# TopSheet.net
KiCad netlist of a schematic drawn in Altium Designer
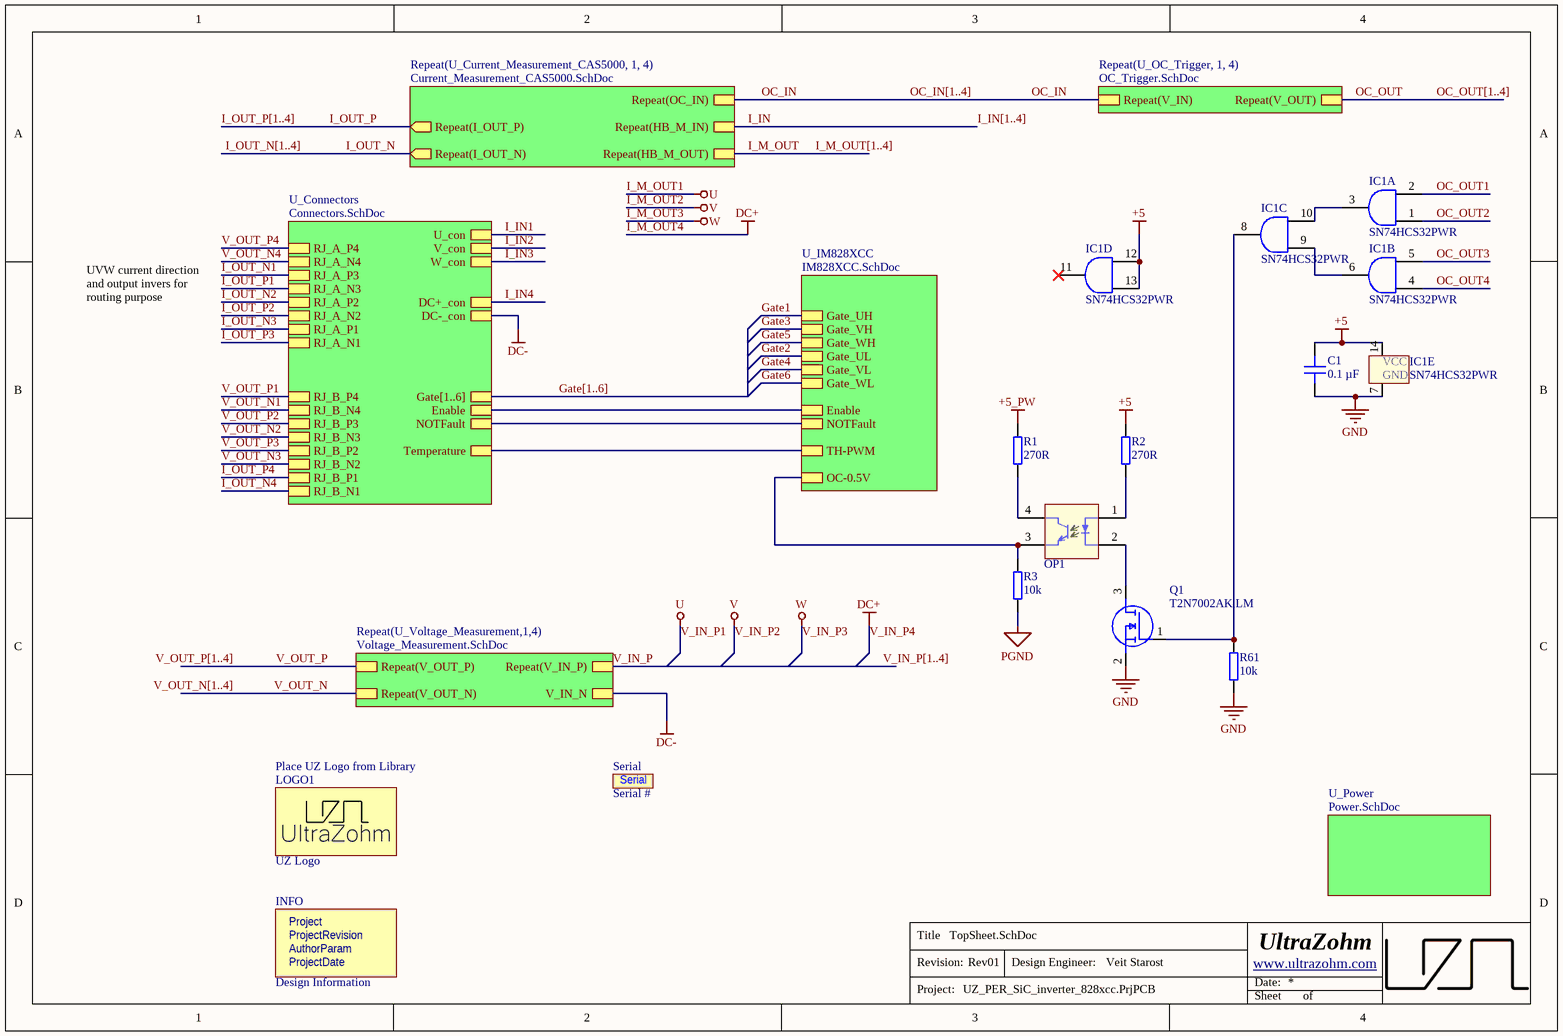
[diagram p0: TopSheet.SchDoc]

(export (version "E")
  (design (tool "Eeschema 10.0.6"))
  (components
    (comp (ref "C1")
      (value "0.1 µF")
      (footprint "C_0603")
      (description "Capacitor 0603, 50 VDC, 0.1 µF, X7R")
      (fields
        (field (name "MANUFACTURER PART NUMBER") "C0603X104K5RAC7411")
        (field (name "MANUFACTURER") "KEMET")
        (field (name "CREATED FROM") "MGremer")
      )
      (libsource (lib "user") (part "Capacitor"))
    )
    (comp (ref "IC1")
      (value "SN74HCS32PWR")
      (footprint "TSSOP-14")
      (description "Logische Gatter Quadruple 2-input OR gates with Schmitt-trigger inputs 14-TSSOP -40 to 125")
      (fields (field (name "MANUFACTURER") "Texas Instruments") (field (name "CREATED FROM") "VStarost"))
      (libsource (lib "") (part "SN74HCS32PWR_1"))
    )
    (comp (ref "INFO")
      (value "Design Information")
      (footprint "Design_info")
      (fields (field (name "MANUFACTURER") "UltraZohm") (field (name "CREATED FROM") "MGremer"))
      (libsource (lib "user") (part "Design_info"))
    )
    (comp (ref "LOGO1")
      (value "UZ Logo")
      (footprint "UZ_Logo_small")
      (fields
        (field (name "MANUFACTURER PART NUMBER") "Logo small")
        (field (name "MANUFACTURER") "UltraZohm")
        (field (name "CREATED") "Jan2021_Liegmann")
        (field (name "CREATED FROM") "MGremer")
      )
      (libsource (lib "user") (part "UZ Logo"))
    )
    (comp (ref "OP1")
      (value "VO617A-2X017T")
      (footprint "SMD4")
      (description "Transistor-Ausgangsoptokoppler H. Relblty 5300 Vrms 63-125% CTR, VDE")
      (fields (field (name "MANUFACTURER") "Vishay") (field (name "CREATED FROM") "VStarost"))
      (libsource (lib "user") (part "LTV-356T"))
    )
    (comp (ref "Q1")
      (value "T2N7002AK,LM")
      (footprint "SOT-23-3")
      (description "Small-signal MOSFET, n-Channel, 200 mA, 60 V")
      (fields
        (field (name "MANUFACTURER") "Toshiba")
        (field (name "LCSC PART NUMBER") "C516175")
        (field (name "CREATED FROM") "VStarost")
      )
      (libsource (lib "user") (part "BSS138LT3G"))
    )
    (comp (ref "R1")
      (value "270R")
      (footprint "RES 0603_1608")
      (description "SMD resistor E24 series")
      (fields
        (field (name "MANUFACTURER PART NUMBER") "RK73B1JTTDD271J")
        (field (name "MANUFACTURER") "KOA Speer")
        (field (name "CREATED FROM") "MGremer")
      )
      (libsource (lib "user") (part "Resistor"))
    )
    (comp (ref "R2")
      (value "270R")
      (footprint "RES 0603_1608")
      (description "SMD resistor E24 series")
      (fields
        (field (name "MANUFACTURER PART NUMBER") "RK73B1JTTDD271J")
        (field (name "MANUFACTURER") "KOA Speer")
        (field (name "CREATED FROM") "MGremer")
      )
      (libsource (lib "user") (part "Resistor"))
    )
    (comp (ref "R3")
      (value "10k")
      (footprint "RES 0603_1608")
      (description "SMD resistor 1%")
      (fields
        (field (name "MANUFACTURER PART NUMBER") "MCWR06X1002FTL")
        (field (name "MANUFACTURER") "Multicomp PRO")
        (field (name "CREATED FROM") "MGremer")
      )
      (libsource (lib "user") (part "Resistor"))
    )
    (comp (ref "R61")
      (value "10k")
      (footprint "RES 0603_1608")
      (description "SMD resistor 1%")
      (fields
        (field (name "MANUFACTURER PART NUMBER") "MCWR06X1002FTL")
        (field (name "MANUFACTURER") "Multicomp PRO")
        (field (name "CREATED FROM") "MGremer")
      )
      (libsource (lib "user") (part "Resistor"))
    )
    (comp (ref "Serial")
      (value "Serial #")
      (footprint "SERIAL")
      (description "Empty serial number of the PCB. Can be used for manually writing the serial number")
      (libsource (lib "annotation") (part "SerialNumber"))
    )
  )
  (nets
    (net (code "5") (name "+5") (class "Default")
      (node (ref "C1") (pin "2") (pinfunction "2_2") (pintype "passive"))
      (node (ref "IC1") (pin "12") (pinfunction "12_12") (pintype "passive"))
      (node (ref "IC1") (pin "13") (pinfunction "13_13") (pintype "passive"))
      (node (ref "IC1") (pin "14") (pinfunction "14_14") (pintype "passive"))
      (node (ref "R2") (pin "2") (pinfunction "2_2") (pintype "passive"))
    )
    (net (code "6") (name "+5_PW") (class "Default")
      (node (ref "R1") (pin "2") (pinfunction "2_2") (pintype "passive"))
    )
    (net (code "36") (name "/OC-0.5V") (class "Default")
      (node (ref "OP1") (pin "3") (pinfunction "3_3") (pintype "passive"))
      (node (ref "R3") (pin "2") (pinfunction "2_2") (pintype "passive"))
    )
    (net (code "40") (name "/OC_OUT1") (class "Default")
      (node (ref "IC1") (pin "2") (pinfunction "2_2") (pintype "passive"))
    )
    (net (code "41") (name "/OC_OUT2") (class "Default")
      (node (ref "IC1") (pin "1") (pinfunction "1_1") (pintype "passive"))
    )
    (net (code "42") (name "/OC_OUT3") (class "Default")
      (node (ref "IC1") (pin "5") (pinfunction "5_5") (pintype "passive"))
    )
    (net (code "43") (name "/OC_OUT4") (class "Default")
      (node (ref "IC1") (pin "4") (pinfunction "4_4") (pintype "passive"))
    )
    (net (code "62") (name "GND") (class "Default")
      (node (ref "C1") (pin "1") (pinfunction "1_1") (pintype "passive"))
      (node (ref "IC1") (pin "7") (pinfunction "7_7") (pintype "passive"))
      (node (ref "Q1") (pin "2") (pinfunction "S_2") (pintype "passive"))
      (node (ref "R61") (pin "1") (pinfunction "1_1") (pintype "passive"))
    )
    (net (code "63") (name "Net-(IC1-Pad6)") (class "Default")
      (node (ref "IC1") (pin "6") (pinfunction "6_6") (pintype "passive"))
      (node (ref "IC1") (pin "9") (pinfunction "9_9") (pintype "passive"))
    )
    (net (code "64") (name "Net-(IC1-Pad10)") (class "Default")
      (node (ref "IC1") (pin "10") (pinfunction "10_10") (pintype "passive"))
      (node (ref "IC1") (pin "3") (pinfunction "3_3") (pintype "passive"))
    )
    (net (code "65") (name "Net-(OP1-Pad1)") (class "Default")
      (node (ref "OP1") (pin "1") (pinfunction "1_1") (pintype "passive"))
      (node (ref "R2") (pin "1") (pinfunction "1_1") (pintype "passive"))
    )
    (net (code "66") (name "Net-(OP1-Pad4)") (class "Default")
      (node (ref "OP1") (pin "4") (pinfunction "4_4") (pintype "passive"))
      (node (ref "R1") (pin "1") (pinfunction "1_1") (pintype "passive"))
    )
    (net (code "67") (name "Net-(Q1-D)") (class "Default")
      (node (ref "OP1") (pin "2") (pinfunction "2_2") (pintype "passive"))
      (node (ref "Q1") (pin "3") (pinfunction "D_3") (pintype "passive"))
    )
    (net (code "68") (name "Net-(Q1-G)") (class "Default")
      (node (ref "IC1") (pin "8") (pinfunction "8_8") (pintype "passive"))
      (node (ref "Q1") (pin "1") (pinfunction "G_1") (pintype "passive"))
      (node (ref "R61") (pin "2") (pinfunction "2_2") (pintype "passive"))
    )
    (net (code "69") (name "PGND") (class "Default")
      (node (ref "R3") (pin "1") (pinfunction "1_1") (pintype "passive"))
    )
    (net (code "73") (name "unconnected-(IC1-Pad11)") (class "Default")
      (node (ref "IC1") (pin "11") (pinfunction "11_11") (pintype "passive+no_connect"))
    )
  )
)
